# Sheet2.net
KiCad netlist of a schematic drawn in Altium Designer
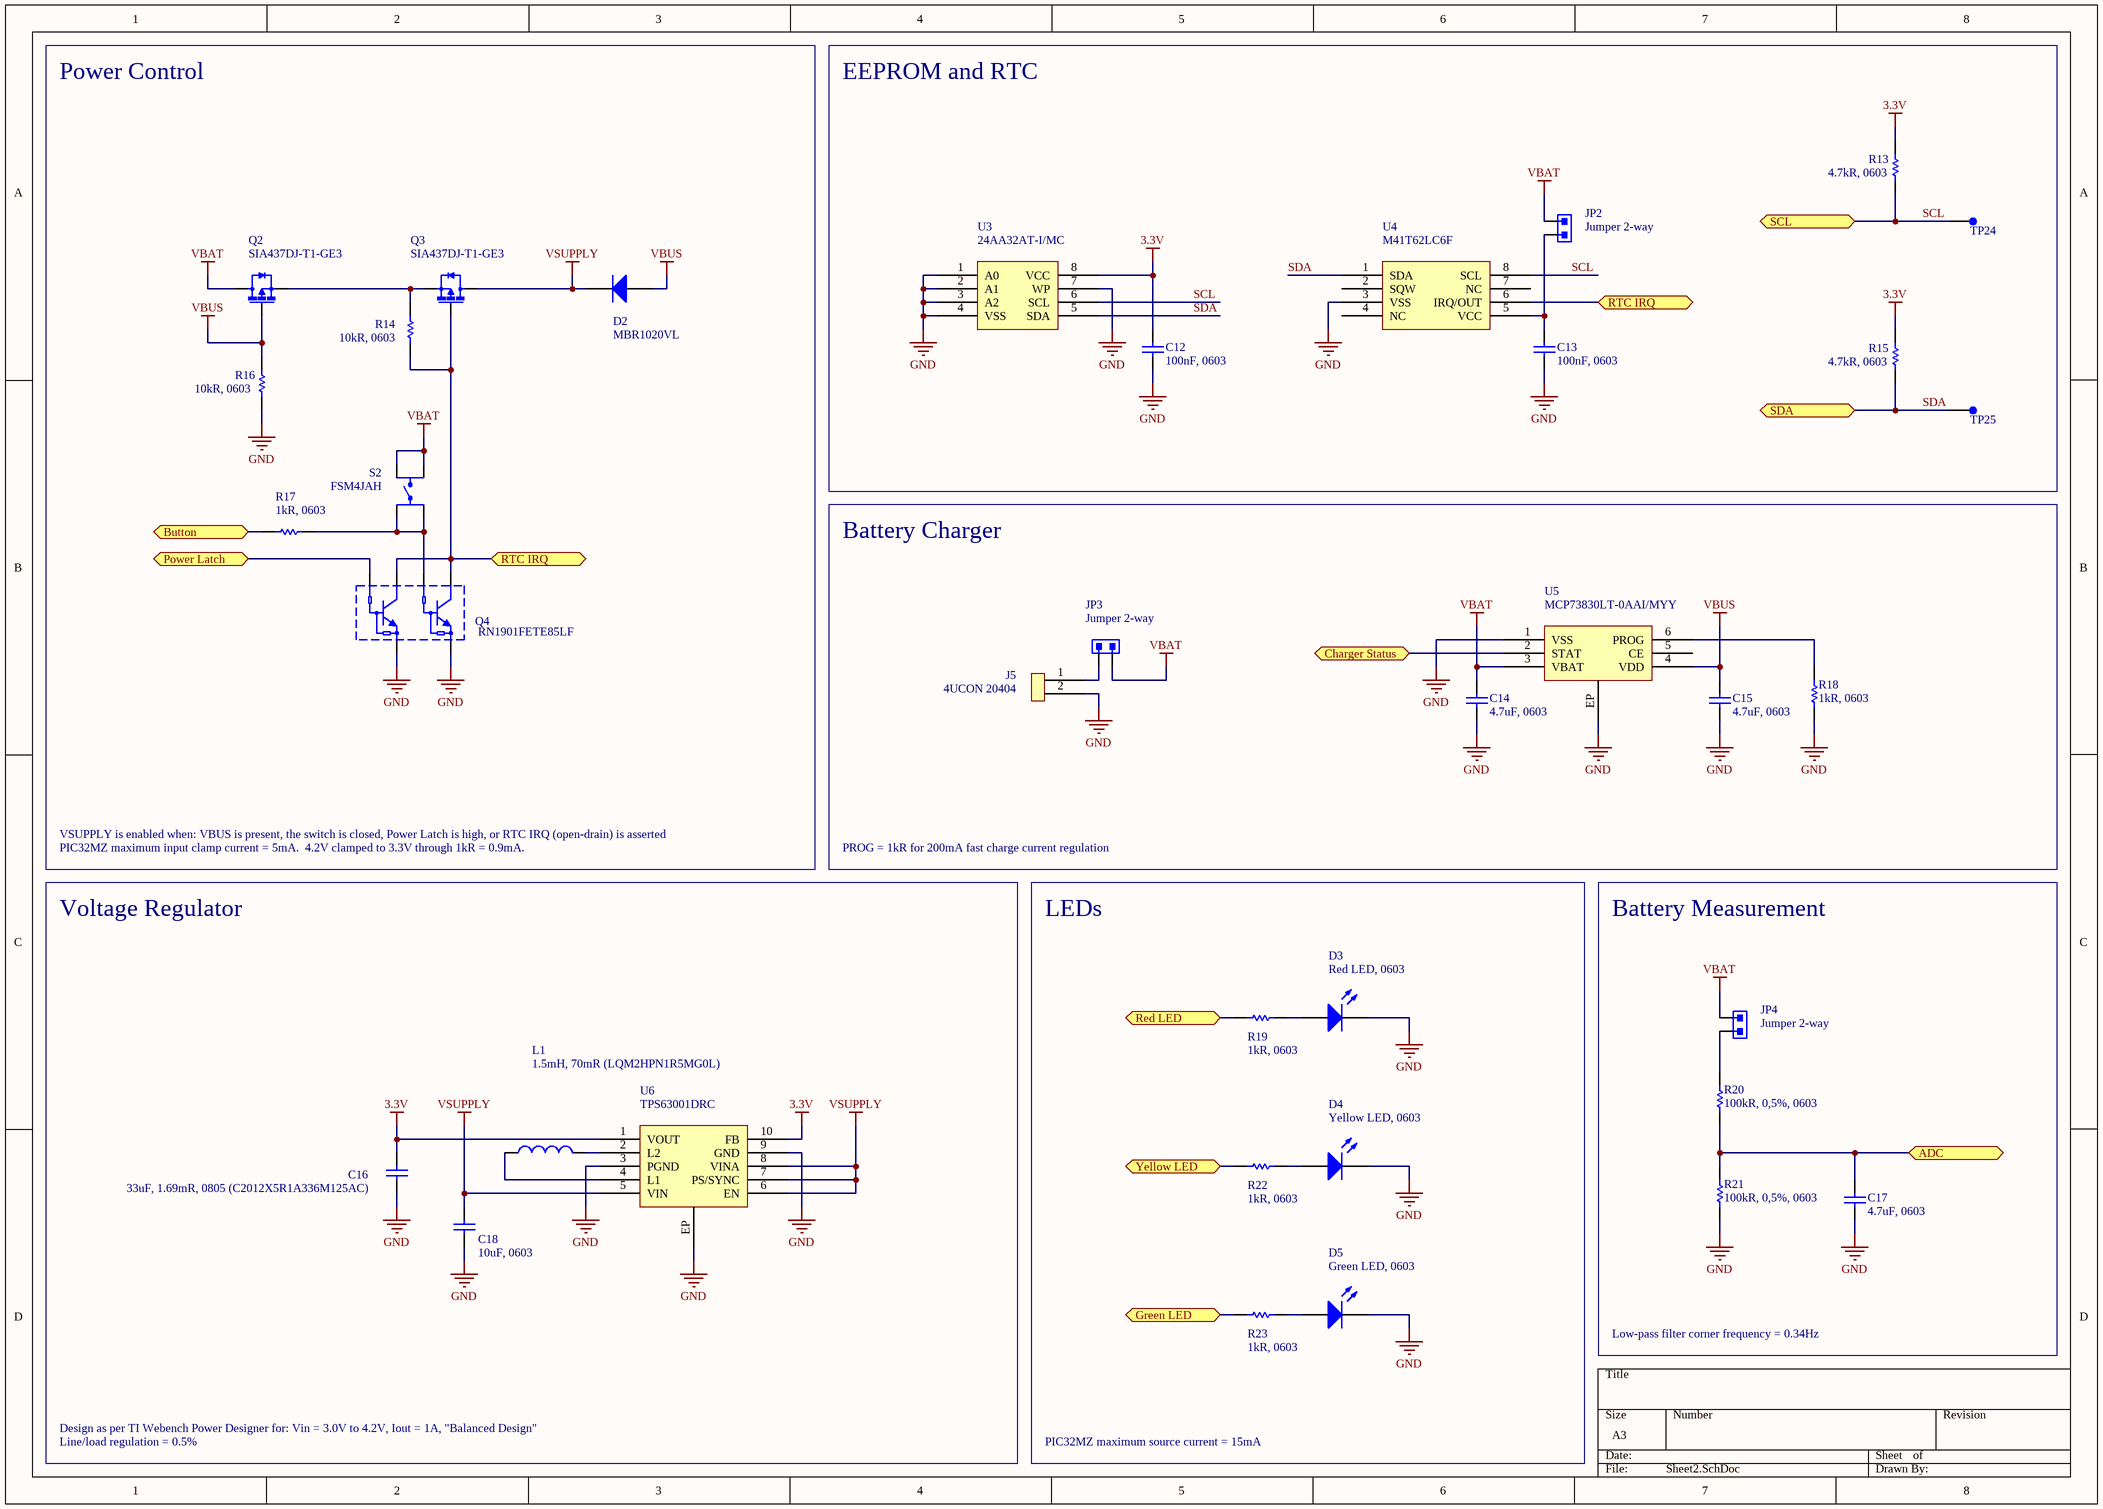
[diagram p0: Sheet2.SchDoc]

(export (version "E")
  (design (tool "Eeschema 10.0.6"))
  (components
    (comp (ref "C12")
      (value "100nF, 0603")
      (footprint "Capacitor 0603")
      (libsource (lib "x-io") (part "Capacitor"))
    )
    (comp (ref "C13")
      (value "100nF, 0603")
      (footprint "Capacitor 0603")
      (libsource (lib "x-io") (part "Capacitor"))
    )
    (comp (ref "C14")
      (value "4.7uF, 0603")
      (footprint "Capacitor 0603")
      (libsource (lib "x-io") (part "Capacitor"))
    )
    (comp (ref "C15")
      (value "4.7uF, 0603")
      (footprint "Capacitor 0603")
      (libsource (lib "x-io") (part "Capacitor"))
    )
    (comp (ref "C16")
      (value "33uF, 1.69mR, 0805 (C2012X5R1A336M125AC)")
      (footprint "Capacitor 0805")
      (libsource (lib "x-io") (part "Capacitor"))
    )
    (comp (ref "C17")
      (value "4.7uF, 0603")
      (footprint "Capacitor 0603")
      (libsource (lib "x-io") (part "Capacitor"))
    )
    (comp (ref "C18")
      (value "10uF, 0603")
      (footprint "Capacitor 0603")
      (libsource (lib "x-io") (part "Capacitor"))
    )
    (comp (ref "D2") (value "MBR1020VL") (footprint "SOD-123") (libsource (lib "x-io") (part "Diode")))
    (comp (ref "D3") (value "Red LED, 0603") (footprint "LED 0603") (libsource (lib "x-io") (part "LED")))
    (comp (ref "D4") (value "Yellow LED, 0603") (footprint "LED 0603") (libsource (lib "x-io") (part "LED")))
    (comp (ref "D5") (value "Green LED, 0603") (footprint "LED 0603") (libsource (lib "x-io") (part "LED")))
    (comp (ref "J5")
      (value "4UCON 20404")
      (footprint "4UCON 20404")
      (libsource (lib "x-io") (part "4UCON 20404"))
    )
    (comp (ref "JP2")
      (value "Jumper 2-way")
      (footprint "Jumper 2-way")
      (libsource (lib "x-io") (part "Jumper 2-way"))
    )
    (comp (ref "JP3")
      (value "Jumper 2-way")
      (footprint "Jumper 2-way")
      (libsource (lib "") (part "Jumper 2-way_1"))
    )
    (comp (ref "JP4")
      (value "Jumper 2-way")
      (footprint "Jumper 2-way")
      (libsource (lib "x-io") (part "Jumper 2-way"))
    )
    (comp (ref "L1")
      (value "1.5mH, 70mR (LQM2HPN1R5MG0L)")
      (footprint "Inductor 1008")
      (libsource (lib "x-io") (part "Inductor"))
    )
    (comp (ref "Q2")
      (value "SIA437DJ-T1-GE3")
      (footprint "SIA437DJ-T1-GE3")
      (libsource (lib "") (part "MOSFET P-Channel_1"))
    )
    (comp (ref "Q3")
      (value "SIA437DJ-T1-GE3")
      (footprint "SIA437DJ-T1-GE3")
      (libsource (lib "x-io") (part "MOSFET P-Channel"))
    )
    (comp (ref "Q4")
      (value "RN1901FETE85LF")
      (footprint "SOT-666")
      (libsource (lib "x-io") (part "RN1901FETE85LF"))
    )
    (comp (ref "R13")
      (value "4.7kR, 0603")
      (footprint "Resistor 0603")
      (libsource (lib "x-io") (part "Resistor"))
    )
    (comp (ref "R14")
      (value "10kR, 0603")
      (footprint "Resistor 0603")
      (libsource (lib "x-io") (part "Resistor"))
    )
    (comp (ref "R15")
      (value "4.7kR, 0603")
      (footprint "Resistor 0603")
      (libsource (lib "x-io") (part "Resistor"))
    )
    (comp (ref "R16")
      (value "10kR, 0603")
      (footprint "Resistor 0603")
      (libsource (lib "x-io") (part "Resistor"))
    )
    (comp (ref "R17")
      (value "1kR, 0603")
      (footprint "Resistor 0603")
      (libsource (lib "x-io") (part "Resistor"))
    )
    (comp (ref "R18")
      (value "1kR, 0603")
      (footprint "Resistor 0603")
      (libsource (lib "x-io") (part "Resistor"))
    )
    (comp (ref "R19")
      (value "1kR, 0603")
      (footprint "Resistor 0603")
      (libsource (lib "x-io") (part "Resistor"))
    )
    (comp (ref "R20")
      (value "100kR, 0,5%, 0603")
      (footprint "Resistor 0603")
      (libsource (lib "x-io") (part "Resistor"))
    )
    (comp (ref "R21")
      (value "100kR, 0,5%, 0603")
      (footprint "Resistor 0603")
      (libsource (lib "x-io") (part "Resistor"))
    )
    (comp (ref "R22")
      (value "1kR, 0603")
      (footprint "Resistor 0603")
      (libsource (lib "x-io") (part "Resistor"))
    )
    (comp (ref "R23")
      (value "1kR, 0603")
      (footprint "Resistor 0603")
      (libsource (lib "x-io") (part "Resistor"))
    )
    (comp (ref "S2") (value "FSM4JAH") (footprint "FSM4JHX") (libsource (lib "x-io") (part "Tactile Switch")))
    (comp (ref "TP24")
      (value "Test Point")
      (footprint "Test Point 1.5mm")
      (libsource (lib "x-io") (part "Test Point"))
    )
    (comp (ref "TP25")
      (value "Test Point")
      (footprint "Test Point 1.5mm")
      (libsource (lib "x-io") (part "Test Point"))
    )
    (comp (ref "U3")
      (value "24AA32AT-I/MC")
      (footprint "TDFN-8 2x3mm")
      (libsource (lib "x-io") (part "24AA32AT-I/MC"))
    )
    (comp (ref "U4")
      (value "M41T62LC6F")
      (footprint "M41T62LC6F")
      (libsource (lib "x-io") (part "M41T62LC6F"))
    )
    (comp (ref "U5")
      (value "MCP73830LT-0AAI/MYY")
      (footprint "TDFN-6 2x2mm")
      (libsource (lib "x-io") (part "MCP73830LT-0AAI/MYY"))
    )
    (comp (ref "U6")
      (value "TPS63001DRC")
      (footprint "VSON-10")
      (libsource (lib "x-io") (part "TPS63001DRC"))
    )
  )
  (nets
    (net (code "1") (name "/ADC") (class "Default")
      (node (ref "C17") (pin "2") (pinfunction "2_2") (pintype "passive"))
      (node (ref "R20") (pin "1") (pinfunction "1_1") (pintype "passive"))
      (node (ref "R21") (pin "2") (pinfunction "2_2") (pintype "passive"))
    )
    (net (code "2") (name "/Button") (class "Default")
      (node (ref "R17") (pin "2") (pinfunction "2_2") (pintype "passive"))
    )
    (net (code "3") (name "/Charger Status") (class "Default")
      (node (ref "U5") (pin "2") (pinfunction "STAT_2") (pintype "passive"))
    )
    (net (code "4") (name "/Green LED") (class "Default")
      (node (ref "R23") (pin "2") (pinfunction "2_2") (pintype "passive"))
    )
    (net (code "5") (name "/Power Latch") (class "Default")
      (node (ref "Q4") (pin "2") (pinfunction "B1_2") (pintype "passive"))
    )
    (net (code "6") (name "/RTC IRQ") (class "Default")
      (node (ref "Q3") (pin "G") (pinfunction "G_G") (pintype "passive"))
      (node (ref "Q4") (pin "3") (pinfunction "C2_3") (pintype "passive"))
      (node (ref "Q4") (pin "6") (pinfunction "C1_6") (pintype "passive"))
      (node (ref "R14") (pin "2") (pinfunction "2_2") (pintype "passive"))
      (node (ref "U4") (pin "6") (pinfunction "IRQ/OUT_6") (pintype "passive"))
    )
    (net (code "7") (name "/Red LED") (class "Default")
      (node (ref "R19") (pin "2") (pinfunction "2_2") (pintype "passive"))
    )
    (net (code "8") (name "/SCL") (class "Default")
      (node (ref "R13") (pin "1") (pinfunction "1_1") (pintype "passive"))
      (node (ref "TP24") (pin "1") (pinfunction "1_1") (pintype "passive"))
      (node (ref "U3") (pin "6") (pinfunction "SCL_6") (pintype "passive"))
      (node (ref "U4") (pin "8") (pinfunction "SCL_8") (pintype "passive"))
    )
    (net (code "9") (name "/SDA") (class "Default")
      (node (ref "R15") (pin "1") (pinfunction "1_1") (pintype "passive"))
      (node (ref "TP25") (pin "1") (pinfunction "1_1") (pintype "passive"))
      (node (ref "U3") (pin "5") (pinfunction "SDA_5") (pintype "passive"))
      (node (ref "U4") (pin "1") (pinfunction "SDA_1") (pintype "passive"))
    )
    (net (code "10") (name "/Yellow LED") (class "Default")
      (node (ref "R22") (pin "2") (pinfunction "2_2") (pintype "passive"))
    )
    (net (code "11") (name "3.3V") (class "Default")
      (node (ref "C12") (pin "2") (pinfunction "2_2") (pintype "passive"))
      (node (ref "C16") (pin "1") (pinfunction "1_1") (pintype "passive"))
      (node (ref "R13") (pin "2") (pinfunction "2_2") (pintype "passive"))
      (node (ref "R15") (pin "2") (pinfunction "2_2") (pintype "passive"))
      (node (ref "U3") (pin "8") (pinfunction "VCC_8") (pintype "passive"))
      (node (ref "U6") (pin "1") (pinfunction "VOUT_1") (pintype "passive"))
      (node (ref "U6") (pin "10") (pinfunction "FB_10") (pintype "passive"))
    )
    (net (code "12") (name "GND") (class "Default")
      (node (ref "C12") (pin "1") (pinfunction "1_1") (pintype "passive"))
      (node (ref "C13") (pin "1") (pinfunction "1_1") (pintype "passive"))
      (node (ref "C14") (pin "1") (pinfunction "1_1") (pintype "passive"))
      (node (ref "C15") (pin "1") (pinfunction "1_1") (pintype "passive"))
      (node (ref "C16") (pin "2") (pinfunction "2_2") (pintype "passive"))
      (node (ref "C17") (pin "1") (pinfunction "1_1") (pintype "passive"))
      (node (ref "C18") (pin "1") (pinfunction "1_1") (pintype "passive"))
      (node (ref "D3") (pin "K") (pinfunction "K_K") (pintype "passive"))
      (node (ref "D4") (pin "K") (pinfunction "K_K") (pintype "passive"))
      (node (ref "D5") (pin "K") (pinfunction "K_K") (pintype "passive"))
      (node (ref "J5") (pin "2") (pinfunction "2_2") (pintype "passive"))
      (node (ref "Q4") (pin "1") (pinfunction "E1_1") (pintype "passive"))
      (node (ref "Q4") (pin "4") (pinfunction "E2_4") (pintype "passive"))
      (node (ref "R16") (pin "1") (pinfunction "1_1") (pintype "passive"))
      (node (ref "R18") (pin "1") (pinfunction "1_1") (pintype "passive"))
      (node (ref "R21") (pin "1") (pinfunction "1_1") (pintype "passive"))
      (node (ref "U3") (pin "1") (pinfunction "A0_1") (pintype "passive"))
      (node (ref "U3") (pin "2") (pinfunction "A1_2") (pintype "passive"))
      (node (ref "U3") (pin "3") (pinfunction "A2_3") (pintype "passive"))
      (node (ref "U3") (pin "4") (pinfunction "VSS_4") (pintype "passive"))
      (node (ref "U3") (pin "7") (pinfunction "WP_7") (pintype "passive"))
      (node (ref "U4") (pin "3") (pinfunction "VSS_3") (pintype "passive"))
      (node (ref "U5") (pin "1") (pinfunction "VSS_1") (pintype "passive"))
      (node (ref "U5") (pin "EP") (pinfunction "EP_EP") (pintype "passive"))
      (node (ref "U6") (pin "3") (pinfunction "PGND_3") (pintype "passive"))
      (node (ref "U6") (pin "9") (pinfunction "GND_9") (pintype "passive"))
      (node (ref "U6") (pin "EP") (pinfunction "EP_EP") (pintype "passive"))
    )
    (net (code "13") (name "Net-(D3-PadA)") (class "Default")
      (node (ref "D3") (pin "A") (pinfunction "A_A") (pintype "passive"))
      (node (ref "R19") (pin "1") (pinfunction "1_1") (pintype "passive"))
    )
    (net (code "14") (name "Net-(D4-PadA)") (class "Default")
      (node (ref "D4") (pin "A") (pinfunction "A_A") (pintype "passive"))
      (node (ref "R22") (pin "1") (pinfunction "1_1") (pintype "passive"))
    )
    (net (code "15") (name "Net-(D5-PadA)") (class "Default")
      (node (ref "D5") (pin "A") (pinfunction "A_A") (pintype "passive"))
      (node (ref "R23") (pin "1") (pinfunction "1_1") (pintype "passive"))
    )
    (net (code "16") (name "Net-(J5-Pad1)") (class "Default")
      (node (ref "J5") (pin "1") (pinfunction "1_1") (pintype "passive"))
      (node (ref "JP3") (pin "1") (pinfunction "1_1") (pintype "passive"))
    )
    (net (code "17") (name "Net-(JP4-Pad2)") (class "Default")
      (node (ref "JP4") (pin "2") (pinfunction "2_2") (pintype "passive"))
      (node (ref "R20") (pin "2") (pinfunction "2_2") (pintype "passive"))
    )
    (net (code "18") (name "Net-(Q2-PadS)") (class "Default")
      (node (ref "Q2") (pin "S") (pinfunction "S_S") (pintype "passive"))
      (node (ref "Q3") (pin "S") (pinfunction "S_S") (pintype "passive"))
      (node (ref "R14") (pin "1") (pinfunction "1_1") (pintype "passive"))
    )
    (net (code "19") (name "Net-(Q4-B2)") (class "Default")
      (node (ref "Q4") (pin "5") (pinfunction "B2_5") (pintype "passive"))
      (node (ref "R17") (pin "1") (pinfunction "1_1") (pintype "passive"))
      (node (ref "S2") (pin "1") (pinfunction "1_1") (pintype "passive"))
      (node (ref "S2") (pin "2") (pinfunction "2_2") (pintype "passive"))
    )
    (net (code "20") (name "Net-(U4-VCC)") (class "Default")
      (node (ref "C13") (pin "2") (pinfunction "2_2") (pintype "passive"))
      (node (ref "JP2") (pin "2") (pinfunction "2_2") (pintype "passive"))
      (node (ref "U4") (pin "5") (pinfunction "VCC_5") (pintype "passive"))
    )
    (net (code "21") (name "Net-(U5-PROG)") (class "Default")
      (node (ref "R18") (pin "2") (pinfunction "2_2") (pintype "passive"))
      (node (ref "U5") (pin "6") (pinfunction "PROG_6") (pintype "passive"))
    )
    (net (code "22") (name "Net-(U6-L1)") (class "Default")
      (node (ref "L1") (pin "1") (pinfunction "1_1") (pintype "passive"))
      (node (ref "U6") (pin "4") (pinfunction "L1_4") (pintype "passive"))
    )
    (net (code "23") (name "Net-(U6-L2)") (class "Default")
      (node (ref "L1") (pin "2") (pinfunction "2_2") (pintype "passive"))
      (node (ref "U6") (pin "2") (pinfunction "L2_2") (pintype "passive"))
    )
    (net (code "24") (name "VBAT") (class "Default")
      (node (ref "C14") (pin "2") (pinfunction "2_2") (pintype "passive"))
      (node (ref "JP2") (pin "1") (pinfunction "1_1") (pintype "passive"))
      (node (ref "JP3") (pin "2") (pinfunction "2_2") (pintype "passive"))
      (node (ref "JP4") (pin "1") (pinfunction "1_1") (pintype "passive"))
      (node (ref "Q2") (pin "D") (pinfunction "D_D") (pintype "passive"))
      (node (ref "S2") (pin "3") (pinfunction "3_3") (pintype "passive"))
      (node (ref "S2") (pin "4") (pinfunction "4_4") (pintype "passive"))
      (node (ref "U5") (pin "3") (pinfunction "VBAT_3") (pintype "passive"))
    )
    (net (code "25") (name "VBUS") (class "Default")
      (node (ref "C15") (pin "2") (pinfunction "2_2") (pintype "passive"))
      (node (ref "D2") (pin "A") (pinfunction "A_A") (pintype "passive"))
      (node (ref "Q2") (pin "G") (pinfunction "G_G") (pintype "passive"))
      (node (ref "R16") (pin "2") (pinfunction "2_2") (pintype "passive"))
      (node (ref "U5") (pin "4") (pinfunction "VDD_4") (pintype "passive"))
    )
    (net (code "26") (name "VSUPPLY") (class "Default")
      (node (ref "C18") (pin "2") (pinfunction "2_2") (pintype "passive"))
      (node (ref "D2") (pin "K") (pinfunction "K_K") (pintype "passive"))
      (node (ref "Q3") (pin "D") (pinfunction "D_D") (pintype "passive"))
      (node (ref "U6") (pin "5") (pinfunction "VIN_5") (pintype "passive"))
      (node (ref "U6") (pin "6") (pinfunction "EN_6") (pintype "passive"))
      (node (ref "U6") (pin "7") (pinfunction "PS/SYNC_7") (pintype "passive"))
      (node (ref "U6") (pin "8") (pinfunction "VINA_8") (pintype "passive"))
    )
    (net (code "27") (name "unconnected-(U4-NC-Pad4)") (class "Default")
      (node (ref "U4") (pin "4") (pinfunction "NC_4") (pintype "passive"))
    )
    (net (code "28") (name "unconnected-(U4-NC-Pad7)") (class "Default")
      (node (ref "U4") (pin "7") (pinfunction "NC_7") (pintype "passive"))
    )
    (net (code "29") (name "unconnected-(U4-SQW-Pad2)") (class "Default")
      (node (ref "U4") (pin "2") (pinfunction "SQW_2") (pintype "passive"))
    )
    (net (code "30") (name "unconnected-(U5-CE-Pad5)") (class "Default")
      (node (ref "U5") (pin "5") (pinfunction "CE_5") (pintype "passive"))
    )
  )
)
